# midi2cv.net
KiCad netlist of a schematic drawn in EAGLE
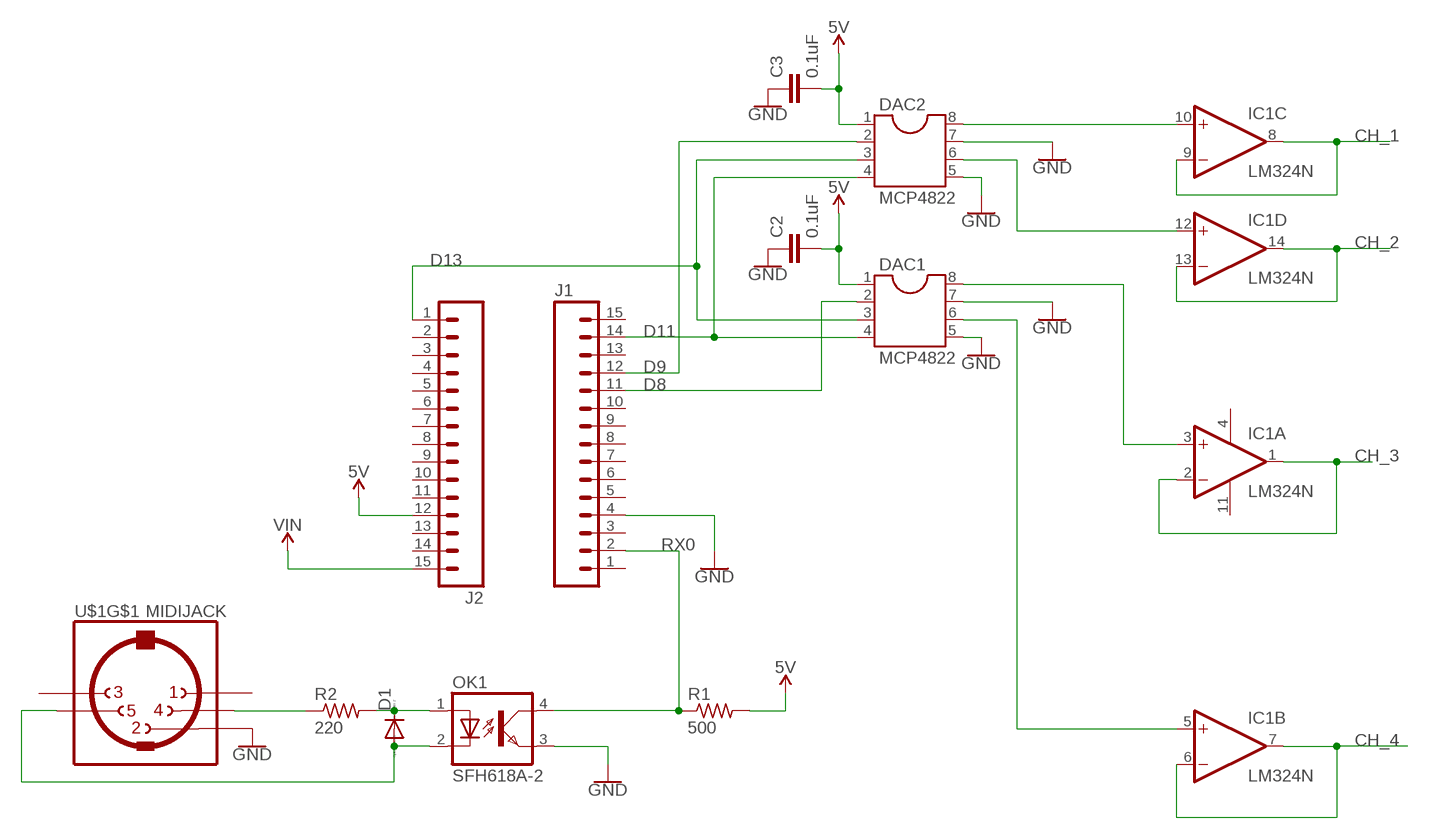
[diagram p0: schematic, sheet 1]

(export (version "E")
  (design (tool "Eeschema 10.0.6"))
  (components
    (comp (ref "C2")
      (value "0.1uF")
      (footprint "eagle-import:CAP-PTH-SMALL-KIT")
      (libsource (lib "eagle-import") (part "0.1UF-KIT-EZ-50V-20%"))
    )
    (comp (ref "C3")
      (value "0.1uF")
      (footprint "eagle-import:CAP-PTH-SMALL-KIT")
      (libsource (lib "eagle-import") (part "0.1UF-KIT-EZ-50V-20%"))
    )
    (comp (ref "D1")
      (value "DIODE-D-10")
      (footprint "eagle-import:D-10")
      (libsource (lib "eagle-import") (part "DIODE-D-10"))
    )
    (comp (ref "DAC1")
      (value "MCP4822")
      (footprint "eagle-import:SOCKET-08")
      (libsource (lib "eagle-import") (part "DIL8S"))
    )
    (comp (ref "DAC2")
      (value "MCP4822")
      (footprint "eagle-import:SOCKET-08")
      (libsource (lib "eagle-import") (part "DIL8S"))
    )
    (comp (ref "IC1")
      (value "LM324N")
      (footprint "eagle-import:DIL14")
      (libsource (lib "eagle-import") (part "LM324N"))
    )
    (comp (ref "J1")
      (value "M15")
      (footprint "eagle-import:1X15")
      (libsource (lib "eagle-import") (part "M15"))
    )
    (comp (ref "J2")
      (value "M15")
      (footprint "eagle-import:1X15")
      (libsource (lib "eagle-import") (part "M15"))
    )
    (comp (ref "OK1")
      (value "SFH618A-2")
      (footprint "eagle-import:DIP4")
      (fields (field (name "MF") "VISHAY/TELEFUNKEN"))
      (libsource (lib "eagle-import") (part "SFH618?A-2"))
    )
    (comp (ref "R1")
      (value "500")
      (footprint "eagle-import:0207_10")
      (libsource (lib "eagle-import") (part "R-US_0207/10"))
    )
    (comp (ref "R2")
      (value "220")
      (footprint "eagle-import:0207_10")
      (libsource (lib "eagle-import") (part "R-US_0207/10"))
    )
    (comp (ref "U$1")
      (value "MIDIJACK")
      (footprint "eagle-import:CP-2350")
      (libsource (lib "eagle-import") (part "MIDIJACK"))
    )
  )
  (nets
    (net (code "1") (name "/CH_1") (class "Default")
      (node (ref "IC1") (pin "8") (pinfunction "OUT_8") (pintype "output"))
      (node (ref "IC1") (pin "9") (pinfunction "-IN_9") (pintype "input"))
    )
    (net (code "2") (name "/CH_2") (class "Default")
      (node (ref "IC1") (pin "13") (pinfunction "-IN_13") (pintype "input"))
      (node (ref "IC1") (pin "14") (pinfunction "OUT_14") (pintype "output"))
    )
    (net (code "3") (name "/CH_3") (class "Default")
      (node (ref "IC1") (pin "1") (pinfunction "OUT_1") (pintype "output"))
      (node (ref "IC1") (pin "2") (pinfunction "-IN_2") (pintype "input"))
    )
    (net (code "4") (name "/CH_4") (class "Default")
      (node (ref "IC1") (pin "6") (pinfunction "-IN_6") (pintype "input"))
      (node (ref "IC1") (pin "7") (pinfunction "OUT_7") (pintype "output"))
    )
    (net (code "5") (name "/D8") (class "Default")
      (node (ref "DAC1") (pin "2") (pinfunction "2_2") (pintype "passive"))
      (node (ref "J1") (pin "11") (pinfunction "11_11") (pintype "passive"))
    )
    (net (code "6") (name "/D9") (class "Default")
      (node (ref "DAC2") (pin "2") (pinfunction "2_2") (pintype "passive"))
      (node (ref "J1") (pin "12") (pinfunction "12_12") (pintype "passive"))
    )
    (net (code "7") (name "/D11") (class "Default")
      (node (ref "DAC1") (pin "4") (pinfunction "4_4") (pintype "passive"))
      (node (ref "DAC2") (pin "4") (pinfunction "4_4") (pintype "passive"))
      (node (ref "J1") (pin "14") (pinfunction "14_14") (pintype "passive"))
    )
    (net (code "8") (name "/D13") (class "Default")
      (node (ref "DAC1") (pin "3") (pinfunction "3_3") (pintype "passive"))
      (node (ref "DAC2") (pin "3") (pinfunction "3_3") (pintype "passive"))
      (node (ref "J2") (pin "1") (pinfunction "1_1") (pintype "passive"))
    )
    (net (code "9") (name "/RX0") (class "Default")
      (node (ref "J1") (pin "2") (pinfunction "2_2") (pintype "passive"))
      (node (ref "OK1") (pin "4") (pinfunction "COL_4") (pintype "passive"))
      (node (ref "R1") (pin "1") (pinfunction "1_1") (pintype "passive"))
    )
    (net (code "10") (name "/V+") (class "Default")
      (node (ref "IC1") (pin "4") (pinfunction "V+_4") (pintype "power_in"))
    )
    (net (code "11") (name "/V-") (class "Default")
      (node (ref "IC1") (pin "11") (pinfunction "V-_11") (pintype "power_in"))
    )
    (net (code "12") (name "5V") (class "Default")
      (node (ref "C2") (pin "2") (pinfunction "2_2") (pintype "passive"))
      (node (ref "C3") (pin "2") (pinfunction "2_2") (pintype "passive"))
      (node (ref "DAC1") (pin "1") (pinfunction "1_1") (pintype "passive"))
      (node (ref "DAC2") (pin "1") (pinfunction "1_1") (pintype "passive"))
      (node (ref "J2") (pin "12") (pinfunction "12_12") (pintype "passive"))
      (node (ref "R1") (pin "2") (pinfunction "2_2") (pintype "passive"))
    )
    (net (code "13") (name "GND") (class "Default")
      (node (ref "C2") (pin "1") (pinfunction "1_1") (pintype "passive"))
      (node (ref "C3") (pin "1") (pinfunction "1_1") (pintype "passive"))
      (node (ref "DAC1") (pin "5") (pinfunction "5_5") (pintype "passive"))
      (node (ref "DAC1") (pin "7") (pinfunction "7_7") (pintype "passive"))
      (node (ref "DAC2") (pin "5") (pinfunction "5_5") (pintype "passive"))
      (node (ref "DAC2") (pin "7") (pinfunction "7_7") (pintype "passive"))
      (node (ref "J1") (pin "4") (pinfunction "4_4") (pintype "passive"))
      (node (ref "OK1") (pin "3") (pinfunction "EMIT_3") (pintype "passive"))
      (node (ref "U$1") (pin "2") (pinfunction "2_2") (pintype "passive"))
    )
    (net (code "14") (name "Net-(IC1A-+IN)") (class "Default")
      (node (ref "DAC1") (pin "8") (pinfunction "8_8") (pintype "passive"))
      (node (ref "IC1") (pin "3") (pinfunction "+IN_3") (pintype "input"))
    )
    (net (code "15") (name "Net-(IC1B-+IN)") (class "Default")
      (node (ref "DAC1") (pin "6") (pinfunction "6_6") (pintype "passive"))
      (node (ref "IC1") (pin "5") (pinfunction "+IN_5") (pintype "input"))
    )
    (net (code "16") (name "Net-(IC1C-+IN)") (class "Default")
      (node (ref "DAC2") (pin "8") (pinfunction "8_8") (pintype "passive"))
      (node (ref "IC1") (pin "10") (pinfunction "+IN_10") (pintype "input"))
    )
    (net (code "17") (name "Net-(IC1D-+IN)") (class "Default")
      (node (ref "DAC2") (pin "6") (pinfunction "6_6") (pintype "passive"))
      (node (ref "IC1") (pin "12") (pinfunction "+IN_12") (pintype "input"))
    )
    (net (code "18") (name "Net-(OK1-A)") (class "Default")
      (node (ref "D1") (pin "C") (pinfunction "C_C") (pintype "passive"))
      (node (ref "OK1") (pin "1") (pinfunction "A_1") (pintype "passive"))
      (node (ref "R2") (pin "2") (pinfunction "2_2") (pintype "passive"))
    )
    (net (code "19") (name "Net-(OK1-C)") (class "Default")
      (node (ref "D1") (pin "A") (pinfunction "A_A") (pintype "passive"))
      (node (ref "OK1") (pin "2") (pinfunction "C_2") (pintype "passive"))
      (node (ref "U$1") (pin "5") (pinfunction "5_5") (pintype "passive"))
    )
    (net (code "20") (name "Net-(R2-Pad1)") (class "Default")
      (node (ref "R2") (pin "1") (pinfunction "1_1") (pintype "passive"))
      (node (ref "U$1") (pin "4") (pinfunction "4_4") (pintype "passive"))
    )
    (net (code "21") (name "VIN") (class "Default")
      (node (ref "J2") (pin "15") (pinfunction "15_15") (pintype "passive"))
    )
    (net (code "22") (name "unconnected-(J1-Pad1)") (class "Default")
      (node (ref "J1") (pin "1") (pinfunction "1_1") (pintype "passive"))
    )
    (net (code "23") (name "unconnected-(J1-Pad3)") (class "Default")
      (node (ref "J1") (pin "3") (pinfunction "3_3") (pintype "passive"))
    )
    (net (code "24") (name "unconnected-(J1-Pad5)") (class "Default")
      (node (ref "J1") (pin "5") (pinfunction "5_5") (pintype "passive"))
    )
    (net (code "25") (name "unconnected-(J1-Pad6)") (class "Default")
      (node (ref "J1") (pin "6") (pinfunction "6_6") (pintype "passive"))
    )
    (net (code "26") (name "unconnected-(J1-Pad7)") (class "Default")
      (node (ref "J1") (pin "7") (pinfunction "7_7") (pintype "passive"))
    )
    (net (code "27") (name "unconnected-(J1-Pad8)") (class "Default")
      (node (ref "J1") (pin "8") (pinfunction "8_8") (pintype "passive"))
    )
    (net (code "28") (name "unconnected-(J1-Pad9)") (class "Default")
      (node (ref "J1") (pin "9") (pinfunction "9_9") (pintype "passive"))
    )
    (net (code "29") (name "unconnected-(J1-Pad10)") (class "Default")
      (node (ref "J1") (pin "10") (pinfunction "10_10") (pintype "passive"))
    )
    (net (code "30") (name "unconnected-(J1-Pad13)") (class "Default")
      (node (ref "J1") (pin "13") (pinfunction "13_13") (pintype "passive"))
    )
    (net (code "31") (name "unconnected-(J1-Pad15)") (class "Default")
      (node (ref "J1") (pin "15") (pinfunction "15_15") (pintype "passive"))
    )
    (net (code "32") (name "unconnected-(J2-Pad2)") (class "Default")
      (node (ref "J2") (pin "2") (pinfunction "2_2") (pintype "passive"))
    )
    (net (code "33") (name "unconnected-(J2-Pad3)") (class "Default")
      (node (ref "J2") (pin "3") (pinfunction "3_3") (pintype "passive"))
    )
    (net (code "34") (name "unconnected-(J2-Pad4)") (class "Default")
      (node (ref "J2") (pin "4") (pinfunction "4_4") (pintype "passive"))
    )
    (net (code "35") (name "unconnected-(J2-Pad5)") (class "Default")
      (node (ref "J2") (pin "5") (pinfunction "5_5") (pintype "passive"))
    )
    (net (code "36") (name "unconnected-(J2-Pad6)") (class "Default")
      (node (ref "J2") (pin "6") (pinfunction "6_6") (pintype "passive"))
    )
    (net (code "37") (name "unconnected-(J2-Pad7)") (class "Default")
      (node (ref "J2") (pin "7") (pinfunction "7_7") (pintype "passive"))
    )
    (net (code "38") (name "unconnected-(J2-Pad8)") (class "Default")
      (node (ref "J2") (pin "8") (pinfunction "8_8") (pintype "passive"))
    )
    (net (code "39") (name "unconnected-(J2-Pad9)") (class "Default")
      (node (ref "J2") (pin "9") (pinfunction "9_9") (pintype "passive"))
    )
    (net (code "40") (name "unconnected-(J2-Pad10)") (class "Default")
      (node (ref "J2") (pin "10") (pinfunction "10_10") (pintype "passive"))
    )
    (net (code "41") (name "unconnected-(J2-Pad11)") (class "Default")
      (node (ref "J2") (pin "11") (pinfunction "11_11") (pintype "passive"))
    )
    (net (code "42") (name "unconnected-(J2-Pad13)") (class "Default")
      (node (ref "J2") (pin "13") (pinfunction "13_13") (pintype "passive"))
    )
    (net (code "43") (name "unconnected-(J2-Pad14)") (class "Default")
      (node (ref "J2") (pin "14") (pinfunction "14_14") (pintype "passive"))
    )
    (net (code "44") (name "unconnected-(U$1-Pad1)") (class "Default")
      (node (ref "U$1") (pin "1") (pinfunction "1_1") (pintype "passive"))
    )
    (net (code "45") (name "unconnected-(U$1-Pad3)") (class "Default")
      (node (ref "U$1") (pin "3") (pinfunction "3_3") (pintype "passive"))
    )
  )
)
